# Drivers.net
KiCad netlist of a schematic drawn in Altium Designer
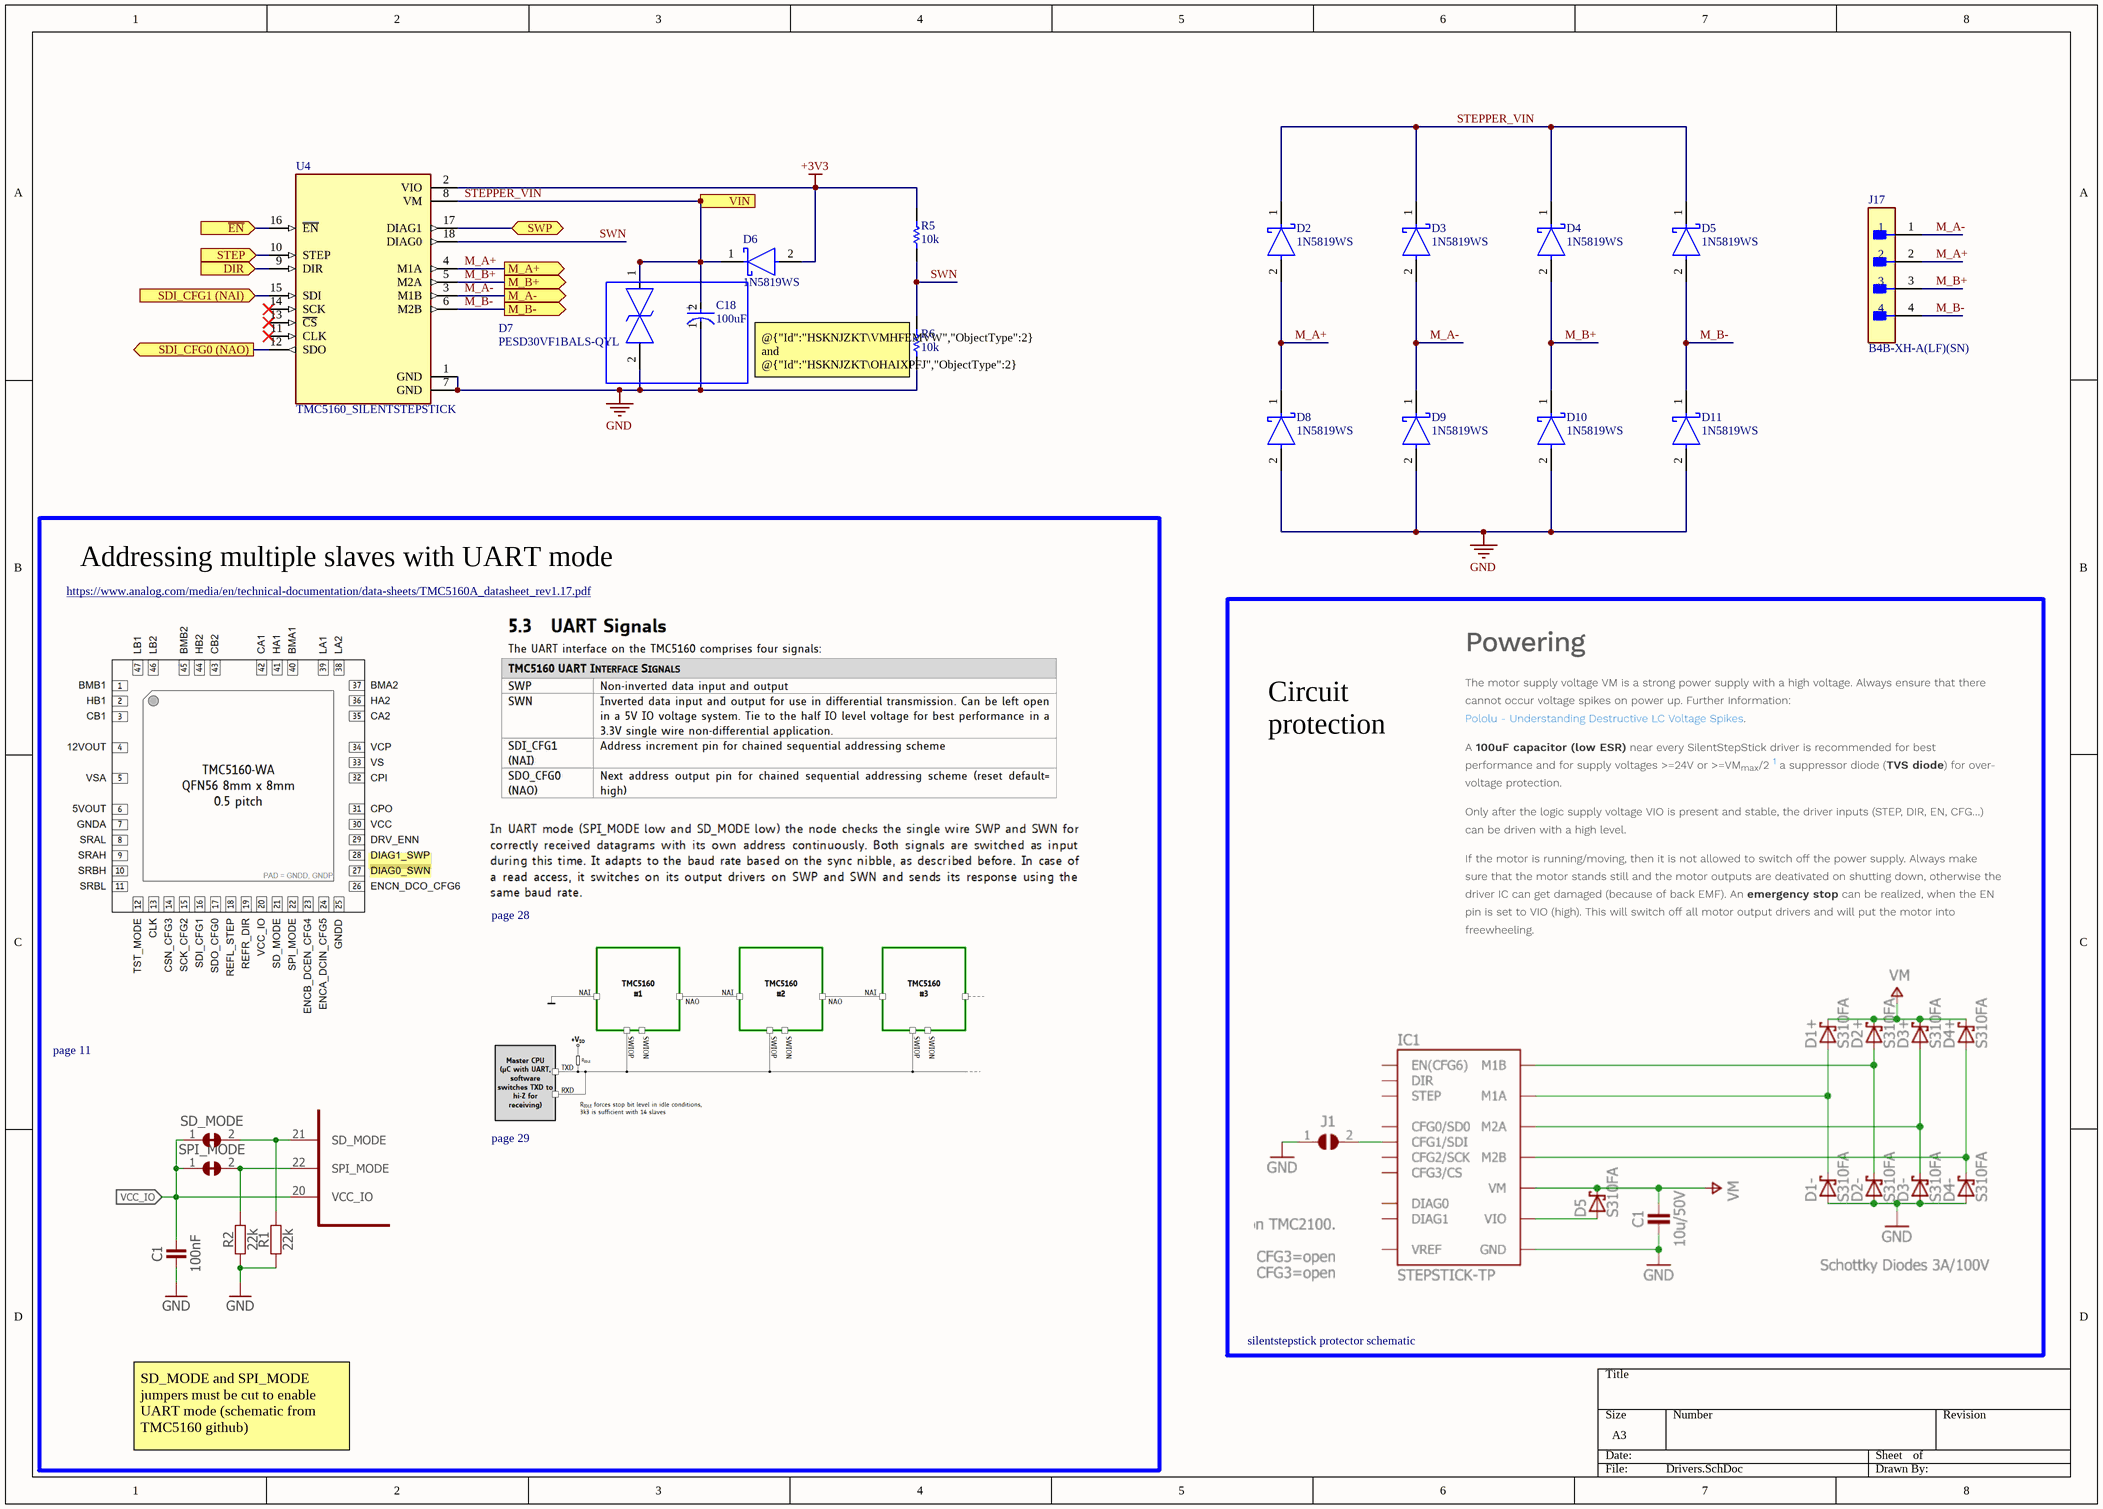
[diagram p0: Drivers.SchDoc]

(export (version "E")
  (design (tool "Eeschema 10.0.6"))
  (components
    (comp (ref "C18")
      (value "100uF")
      (footprint "FP-UWT1H101MNL1GS-MFG")
      (description "CAP ALUM 100UF 20% 50V SMD")
      (fields (field (name "TOLERANCE") "20%") (field (name "VOLTAGE") "50V"))
      (libsource (lib "Altium Content Vault") (part "203bc49f2ac43e59fd269a8c329ed05"))
    )
    (comp (ref "D2")
      (value "1N5819WS")
      (footprint "FP-477-02-MFG")
      (description "40V 600mV@1A 1A SOD-323 Schottky Barrier Diodes (SBD) ROHS")
      (libsource (lib "Altium Content Vault") (part "1d6ec82d83fb6aee721767c19dac4b9"))
    )
    (comp (ref "D3")
      (value "1N5819WS")
      (footprint "FP-477-02-MFG")
      (description "40V 600mV@1A 1A SOD-323 Schottky Barrier Diodes (SBD) ROHS")
      (libsource (lib "Altium Content Vault") (part "1d6ec82d83fb6aee721767c19dac4b9"))
    )
    (comp (ref "D4")
      (value "1N5819WS")
      (footprint "FP-477-02-MFG")
      (description "40V 600mV@1A 1A SOD-323 Schottky Barrier Diodes (SBD) ROHS")
      (libsource (lib "Altium Content Vault") (part "1d6ec82d83fb6aee721767c19dac4b9"))
    )
    (comp (ref "D5")
      (value "1N5819WS")
      (footprint "FP-477-02-MFG")
      (description "40V 600mV@1A 1A SOD-323 Schottky Barrier Diodes (SBD) ROHS")
      (libsource (lib "Altium Content Vault") (part "1d6ec82d83fb6aee721767c19dac4b9"))
    )
    (comp (ref "D6")
      (value "1N5819WS")
      (footprint "FP-477-02-MFG")
      (description "40V 600mV@1A 1A SOD-323 Schottky Barrier Diodes (SBD) ROHS")
      (libsource (lib "Altium Content Vault") (part "1d6ec82d83fb6aee721767c19dac4b9"))
    )
    (comp (ref "D7")
      (value "PESD30VF1BALS-QYL")
      (footprint "PESD30VF1BALSQYL")
      (description "21V (Typ) Clamp Ipp Tvs Diode Surface Mount DFN1006-2")
      (fields (field (name "MOUSER PART NUMBER") "771-PESD30VF1BALSQYL"))
      (libsource (lib "BumbleBee Autonomous Systems - NUS") (part "PESD30VF1BALS-QYL"))
    )
    (comp (ref "D8")
      (value "1N5819WS")
      (footprint "FP-477-02-MFG")
      (description "40V 600mV@1A 1A SOD-323 Schottky Barrier Diodes (SBD) ROHS")
      (libsource (lib "Altium Content Vault") (part "1d6ec82d83fb6aee721767c19dac4b9"))
    )
    (comp (ref "D9")
      (value "1N5819WS")
      (footprint "FP-477-02-MFG")
      (description "40V 600mV@1A 1A SOD-323 Schottky Barrier Diodes (SBD) ROHS")
      (libsource (lib "Altium Content Vault") (part "1d6ec82d83fb6aee721767c19dac4b9"))
    )
    (comp (ref "D10")
      (value "1N5819WS")
      (footprint "FP-477-02-MFG")
      (description "40V 600mV@1A 1A SOD-323 Schottky Barrier Diodes (SBD) ROHS")
      (libsource (lib "Altium Content Vault") (part "1d6ec82d83fb6aee721767c19dac4b9"))
    )
    (comp (ref "D11")
      (value "1N5819WS")
      (footprint "FP-477-02-MFG")
      (description "40V 600mV@1A 1A SOD-323 Schottky Barrier Diodes (SBD) ROHS")
      (libsource (lib "Altium Content Vault") (part "1d6ec82d83fb6aee721767c19dac4b9"))
    )
    (comp (ref "J17")
      (value "B4B-XH-A(LF)(SN)")
      (footprint "FP-B4B-XH-A_LF_SN-MFG")
      (description "CONN HEADER VERT 4POS 2.5MM")
      (libsource (lib "Altium Content Vault") (part "299a8cea1bdcbc3624fe62c390fa72c"))
    )
    (comp (ref "R5")
      (value "0603WAF1002T5E")
      (footprint "RESC1609X50X30NL8T20")
      (description "100mW Thick Film Resistors 75V ±100ppm/℃ ±1% 10kΩ 0603 Chip Resistor - Surface Mount ROHS")
      (fields (field (name "RESISTANCE") "10k"))
      (libsource (lib "Altium Content Vault") (part "RES-2"))
    )
    (comp (ref "R6")
      (value "0603WAF1002T5E")
      (footprint "RESC1609X50X30NL8T20")
      (description "100mW Thick Film Resistors 75V ±100ppm/℃ ±1% 10kΩ 0603 Chip Resistor - Surface Mount ROHS")
      (fields (field (name "RESISTANCE") "10k"))
      (libsource (lib "Altium Content Vault") (part "RES-2"))
    )
    (comp (ref "U4")
      (value "TMC5160_SILENTSTEPSTICK")
      (footprint "MODULE_TMC5160_SILENTSTEPSTICK")
      (description "TMC5160 SilentStepStick Motor Driver")
      (fields (field (name "MF") "Trinamic Motion Control GmbH"))
      (libsource (lib "BumbleBee Autonomous Systems - NUS") (part "TMC5160_SILENTSTEPSTICK"))
    )
  )
  (nets
    (net (code "1") (name "+3V3") (class "Default")
      (node (ref "D6") (pin "2") (pinfunction "A_2") (pintype "passive"))
      (node (ref "R5") (pin "2") (pinfunction "2_2") (pintype "passive"))
      (node (ref "U4") (pin "2") (pinfunction "VIO_2") (pintype "power_in"))
    )
    (net (code "2") (name "/DIR") (class "Default")
      (node (ref "U4") (pin "9") (pinfunction "DIR_9") (pintype "input"))
    )
    (net (code "3") (name "/M_A+") (class "Default")
      (node (ref "D2") (pin "2") (pinfunction "A_2") (pintype "passive"))
      (node (ref "D8") (pin "1") (pinfunction "C_1") (pintype "passive"))
      (node (ref "J17") (pin "2") (pinfunction "2_2") (pintype "passive"))
      (node (ref "U4") (pin "4") (pinfunction "M1A_4") (pintype "output"))
    )
    (net (code "4") (name "/M_A-") (class "Default")
      (node (ref "D3") (pin "2") (pinfunction "A_2") (pintype "passive"))
      (node (ref "D9") (pin "1") (pinfunction "C_1") (pintype "passive"))
      (node (ref "J17") (pin "1") (pinfunction "1_1") (pintype "passive"))
      (node (ref "U4") (pin "3") (pinfunction "M1B_3") (pintype "output"))
    )
    (net (code "5") (name "/M_B+") (class "Default")
      (node (ref "D10") (pin "1") (pinfunction "C_1") (pintype "passive"))
      (node (ref "D4") (pin "2") (pinfunction "A_2") (pintype "passive"))
      (node (ref "J17") (pin "3") (pinfunction "3_3") (pintype "passive"))
      (node (ref "U4") (pin "5") (pinfunction "M2A_5") (pintype "output"))
    )
    (net (code "6") (name "/M_B-") (class "Default")
      (node (ref "D11") (pin "1") (pinfunction "C_1") (pintype "passive"))
      (node (ref "D5") (pin "2") (pinfunction "A_2") (pintype "passive"))
      (node (ref "J17") (pin "4") (pinfunction "4_4") (pintype "passive"))
      (node (ref "U4") (pin "6") (pinfunction "M2B_6") (pintype "output"))
    )
    (net (code "7") (name "/SDI_CFG0 (NAO)") (class "Default")
      (node (ref "U4") (pin "12") (pinfunction "SDO_12") (pintype "output"))
    )
    (net (code "8") (name "/SDI_CFG1 (NAI)") (class "Default")
      (node (ref "U4") (pin "15") (pinfunction "SDI_15") (pintype "input"))
    )
    (net (code "9") (name "/STEP") (class "Default")
      (node (ref "U4") (pin "10") (pinfunction "STEP_10") (pintype "input"))
    )
    (net (code "10") (name "/STEPPER_VIN") (class "Default")
      (node (ref "C18") (pin "2") (pinfunction "A_2") (pintype "passive"))
      (node (ref "D2") (pin "1") (pinfunction "C_1") (pintype "passive"))
      (node (ref "D3") (pin "1") (pinfunction "C_1") (pintype "passive"))
      (node (ref "D4") (pin "1") (pinfunction "C_1") (pintype "passive"))
      (node (ref "D5") (pin "1") (pinfunction "C_1") (pintype "passive"))
      (node (ref "D6") (pin "1") (pinfunction "C_1") (pintype "passive"))
      (node (ref "D7") (pin "1") (pinfunction "1_1") (pintype "passive"))
      (node (ref "U4") (pin "8") (pinfunction "VM_8") (pintype "power_in"))
    )
    (net (code "11") (name "/SWN") (class "Default")
      (node (ref "R5") (pin "1") (pinfunction "1_1") (pintype "passive"))
      (node (ref "R6") (pin "2") (pinfunction "2_2") (pintype "passive"))
      (node (ref "U4") (pin "18") (pinfunction "DIAG0_18") (pintype "output"))
    )
    (net (code "12") (name "/SWP") (class "Default")
      (node (ref "U4") (pin "17") (pinfunction "DIAG1_17") (pintype "output"))
    )
    (net (code "13") (name "/~{EN}") (class "Default")
      (node (ref "U4") (pin "16") (pinfunction "~{EN}_16") (pintype "input"))
    )
    (net (code "14") (name "GND") (class "Default")
      (node (ref "C18") (pin "1") (pinfunction "C_1") (pintype "passive"))
      (node (ref "D10") (pin "2") (pinfunction "A_2") (pintype "passive"))
      (node (ref "D11") (pin "2") (pinfunction "A_2") (pintype "passive"))
      (node (ref "D7") (pin "2") (pinfunction "2_2") (pintype "passive"))
      (node (ref "D8") (pin "2") (pinfunction "A_2") (pintype "passive"))
      (node (ref "D9") (pin "2") (pinfunction "A_2") (pintype "passive"))
      (node (ref "R6") (pin "1") (pinfunction "1_1") (pintype "passive"))
      (node (ref "U4") (pin "1") (pinfunction "GND_1") (pintype "power_in"))
      (node (ref "U4") (pin "7") (pinfunction "GND_7") (pintype "power_in"))
    )
    (net (code "15") (name "unconnected-(U4-CLK-Pad11)") (class "Default")
      (node (ref "U4") (pin "11") (pinfunction "CLK_11") (pintype "input+no_connect"))
    )
    (net (code "16") (name "unconnected-(U4-SCK-Pad14)") (class "Default")
      (node (ref "U4") (pin "14") (pinfunction "SCK_14") (pintype "input+no_connect"))
    )
    (net (code "17") (name "unconnected-(U4-~{CS}-Pad13)") (class "Default")
      (node (ref "U4") (pin "13") (pinfunction "~{CS}_13") (pintype "input+no_connect"))
    )
  )
)
